# PCIE_dual_breakout_2L_v0_2.net
KiCad netlist of a schematic drawn in EAGLE
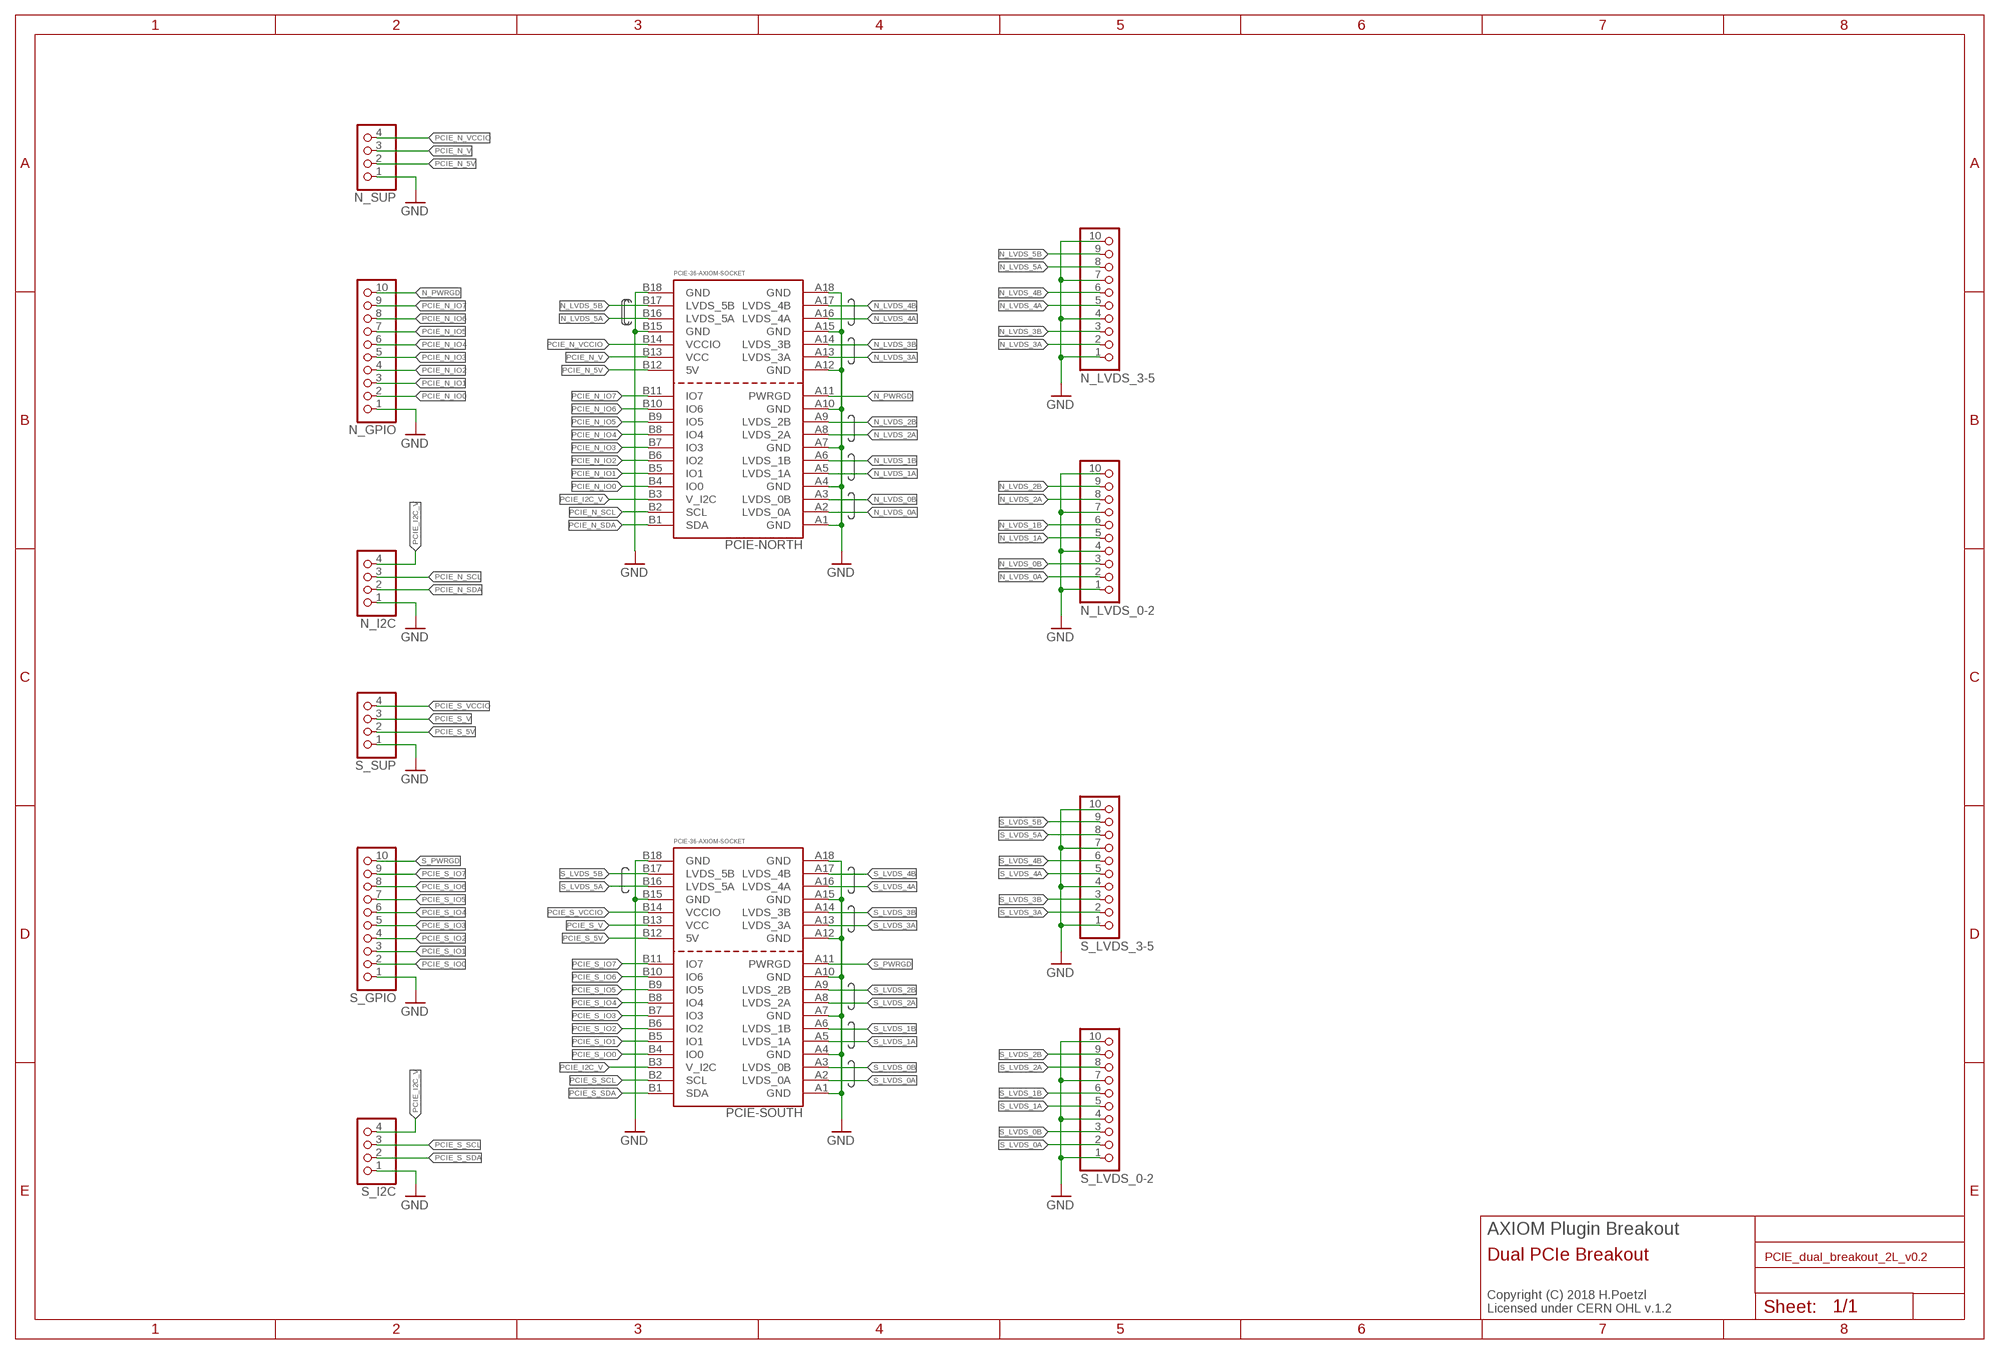
[diagram p0: schematic, sheet 1]

(export (version "E")
  (design (tool "Eeschema 10.0.6"))
  (components
    (comp (ref "N_GPIO")
      (value "PINHD-1X10_2.54-S")
      (footprint "eagle-import:1X10-S")
      (libsource (lib "eagle-import") (part "PINHD-1X10_2.54-S"))
    )
    (comp (ref "N_I2C")
      (value "PINHD-1X04_2.54-S")
      (footprint "eagle-import:1X04-S")
      (libsource (lib "eagle-import") (part "PINHD-1X04_2.54-S"))
    )
    (comp (ref "N_LVDS_0-2")
      (value "PINHD-1X10_2.54-S")
      (footprint "eagle-import:1X10-S")
      (libsource (lib "eagle-import") (part "PINHD-1X10_2.54-S"))
    )
    (comp (ref "N_LVDS_3-5")
      (value "PINHD-1X10_2.54-S")
      (footprint "eagle-import:1X10-S")
      (libsource (lib "eagle-import") (part "PINHD-1X10_2.54-S"))
    )
    (comp (ref "N_SUP")
      (value "PINHD-1X04_2.54-S")
      (footprint "eagle-import:1X04-S")
      (libsource (lib "eagle-import") (part "PINHD-1X04_2.54-S"))
    )
    (comp (ref "PCIE-NORTH")
      (value "PCIE-36-AXIOM-SOCKET")
      (footprint "eagle-import:PCIE-36")
      (libsource (lib "eagle-import") (part "PCIE-36-AXIOM-SOCKET"))
    )
    (comp (ref "PCIE-SOUTH")
      (value "PCIE-36-AXIOM-SOCKET")
      (footprint "eagle-import:PCIE-36")
      (libsource (lib "eagle-import") (part "PCIE-36-AXIOM-SOCKET"))
    )
    (comp (ref "S_GPIO")
      (value "PINHD-1X10_2.54-S")
      (footprint "eagle-import:1X10-S")
      (libsource (lib "eagle-import") (part "PINHD-1X10_2.54-S"))
    )
    (comp (ref "S_I2C")
      (value "PINHD-1X04_2.54-S")
      (footprint "eagle-import:1X04-S")
      (libsource (lib "eagle-import") (part "PINHD-1X04_2.54-S"))
    )
    (comp (ref "S_LVDS_0-2")
      (value "PINHD-1X10_2.54-S")
      (footprint "eagle-import:1X10-S")
      (libsource (lib "eagle-import") (part "PINHD-1X10_2.54-S"))
    )
    (comp (ref "S_LVDS_3-5")
      (value "PINHD-1X10_2.54-S")
      (footprint "eagle-import:1X10-S")
      (libsource (lib "eagle-import") (part "PINHD-1X10_2.54-S"))
    )
    (comp (ref "S_SUP")
      (value "PINHD-1X04_2.54-S")
      (footprint "eagle-import:1X04-S")
      (libsource (lib "eagle-import") (part "PINHD-1X04_2.54-S"))
    )
  )
  (nets
    (net (code "1") (name "GND") (class "Default")
      (node (ref "N_GPIO") (pin "1") (pinfunction "1_1") (pintype "passive"))
      (node (ref "N_I2C") (pin "1") (pinfunction "1_1") (pintype "passive"))
      (node (ref "N_LVDS_0-2") (pin "1") (pinfunction "1_1") (pintype "passive"))
      (node (ref "N_LVDS_0-2") (pin "10") (pinfunction "10_10") (pintype "passive"))
      (node (ref "N_LVDS_0-2") (pin "4") (pinfunction "4_4") (pintype "passive"))
      (node (ref "N_LVDS_0-2") (pin "7") (pinfunction "7_7") (pintype "passive"))
      (node (ref "N_LVDS_3-5") (pin "1") (pinfunction "1_1") (pintype "passive"))
      (node (ref "N_LVDS_3-5") (pin "10") (pinfunction "10_10") (pintype "passive"))
      (node (ref "N_LVDS_3-5") (pin "4") (pinfunction "4_4") (pintype "passive"))
      (node (ref "N_LVDS_3-5") (pin "7") (pinfunction "7_7") (pintype "passive"))
      (node (ref "N_SUP") (pin "1") (pinfunction "1_1") (pintype "passive"))
      (node (ref "PCIE-NORTH") (pin "A1") (pinfunction "GND_A1") (pintype "passive"))
      (node (ref "PCIE-NORTH") (pin "A10") (pinfunction "GND_A10") (pintype "passive"))
      (node (ref "PCIE-NORTH") (pin "A12") (pinfunction "GND_A12") (pintype "passive"))
      (node (ref "PCIE-NORTH") (pin "A15") (pinfunction "GND_A15") (pintype "passive"))
      (node (ref "PCIE-NORTH") (pin "A18") (pinfunction "GND_A18") (pintype "passive"))
      (node (ref "PCIE-NORTH") (pin "A4") (pinfunction "GND_A4") (pintype "passive"))
      (node (ref "PCIE-NORTH") (pin "A7") (pinfunction "GND_A7") (pintype "passive"))
      (node (ref "PCIE-NORTH") (pin "B15") (pinfunction "GND_B15") (pintype "passive"))
      (node (ref "PCIE-NORTH") (pin "B18") (pinfunction "GND_B18") (pintype "passive"))
      (node (ref "PCIE-SOUTH") (pin "A1") (pinfunction "GND_A1") (pintype "passive"))
      (node (ref "PCIE-SOUTH") (pin "A10") (pinfunction "GND_A10") (pintype "passive"))
      (node (ref "PCIE-SOUTH") (pin "A12") (pinfunction "GND_A12") (pintype "passive"))
      (node (ref "PCIE-SOUTH") (pin "A15") (pinfunction "GND_A15") (pintype "passive"))
      (node (ref "PCIE-SOUTH") (pin "A18") (pinfunction "GND_A18") (pintype "passive"))
      (node (ref "PCIE-SOUTH") (pin "A4") (pinfunction "GND_A4") (pintype "passive"))
      (node (ref "PCIE-SOUTH") (pin "A7") (pinfunction "GND_A7") (pintype "passive"))
      (node (ref "PCIE-SOUTH") (pin "B15") (pinfunction "GND_B15") (pintype "passive"))
      (node (ref "PCIE-SOUTH") (pin "B18") (pinfunction "GND_B18") (pintype "passive"))
      (node (ref "S_GPIO") (pin "1") (pinfunction "1_1") (pintype "passive"))
      (node (ref "S_I2C") (pin "1") (pinfunction "1_1") (pintype "passive"))
      (node (ref "S_LVDS_0-2") (pin "1") (pinfunction "1_1") (pintype "passive"))
      (node (ref "S_LVDS_0-2") (pin "10") (pinfunction "10_10") (pintype "passive"))
      (node (ref "S_LVDS_0-2") (pin "4") (pinfunction "4_4") (pintype "passive"))
      (node (ref "S_LVDS_0-2") (pin "7") (pinfunction "7_7") (pintype "passive"))
      (node (ref "S_LVDS_3-5") (pin "1") (pinfunction "1_1") (pintype "passive"))
      (node (ref "S_LVDS_3-5") (pin "10") (pinfunction "10_10") (pintype "passive"))
      (node (ref "S_LVDS_3-5") (pin "4") (pinfunction "4_4") (pintype "passive"))
      (node (ref "S_LVDS_3-5") (pin "7") (pinfunction "7_7") (pintype "passive"))
      (node (ref "S_SUP") (pin "1") (pinfunction "1_1") (pintype "passive"))
    )
    (net (code "2") (name "N_LVDS_0A") (class "Default")
      (node (ref "N_LVDS_0-2") (pin "2") (pinfunction "2_2") (pintype "passive"))
      (node (ref "PCIE-NORTH") (pin "A2") (pinfunction "LVDS_0A_A2") (pintype "passive"))
    )
    (net (code "3") (name "N_LVDS_0B") (class "Default")
      (node (ref "N_LVDS_0-2") (pin "3") (pinfunction "3_3") (pintype "passive"))
      (node (ref "PCIE-NORTH") (pin "A3") (pinfunction "LVDS_0B_A3") (pintype "passive"))
    )
    (net (code "4") (name "N_LVDS_1A") (class "Default")
      (node (ref "N_LVDS_0-2") (pin "5") (pinfunction "5_5") (pintype "passive"))
      (node (ref "PCIE-NORTH") (pin "A5") (pinfunction "LVDS_1A_A5") (pintype "passive"))
    )
    (net (code "5") (name "N_LVDS_1B") (class "Default")
      (node (ref "N_LVDS_0-2") (pin "6") (pinfunction "6_6") (pintype "passive"))
      (node (ref "PCIE-NORTH") (pin "A6") (pinfunction "LVDS_1B_A6") (pintype "passive"))
    )
    (net (code "6") (name "N_LVDS_2A") (class "Default")
      (node (ref "N_LVDS_0-2") (pin "8") (pinfunction "8_8") (pintype "passive"))
      (node (ref "PCIE-NORTH") (pin "A8") (pinfunction "LVDS_2A_A8") (pintype "passive"))
    )
    (net (code "7") (name "N_LVDS_2B") (class "Default")
      (node (ref "N_LVDS_0-2") (pin "9") (pinfunction "9_9") (pintype "passive"))
      (node (ref "PCIE-NORTH") (pin "A9") (pinfunction "LVDS_2B_A9") (pintype "passive"))
    )
    (net (code "8") (name "N_LVDS_3A") (class "Default")
      (node (ref "N_LVDS_3-5") (pin "2") (pinfunction "2_2") (pintype "passive"))
      (node (ref "PCIE-NORTH") (pin "A13") (pinfunction "LVDS_3A_A13") (pintype "passive"))
    )
    (net (code "9") (name "N_LVDS_3B") (class "Default")
      (node (ref "N_LVDS_3-5") (pin "3") (pinfunction "3_3") (pintype "passive"))
      (node (ref "PCIE-NORTH") (pin "A14") (pinfunction "LVDS_3B_A14") (pintype "passive"))
    )
    (net (code "10") (name "N_LVDS_4A") (class "Default")
      (node (ref "N_LVDS_3-5") (pin "5") (pinfunction "5_5") (pintype "passive"))
      (node (ref "PCIE-NORTH") (pin "A16") (pinfunction "LVDS_4A_A16") (pintype "passive"))
    )
    (net (code "11") (name "N_LVDS_4B") (class "Default")
      (node (ref "N_LVDS_3-5") (pin "6") (pinfunction "6_6") (pintype "passive"))
      (node (ref "PCIE-NORTH") (pin "A17") (pinfunction "LVDS_4B_A17") (pintype "passive"))
    )
    (net (code "12") (name "N_LVDS_5A") (class "Default")
      (node (ref "N_LVDS_3-5") (pin "8") (pinfunction "8_8") (pintype "passive"))
      (node (ref "PCIE-NORTH") (pin "B16") (pinfunction "LVDS_5A_B16") (pintype "passive"))
    )
    (net (code "13") (name "N_LVDS_5B") (class "Default")
      (node (ref "N_LVDS_3-5") (pin "9") (pinfunction "9_9") (pintype "passive"))
      (node (ref "PCIE-NORTH") (pin "B17") (pinfunction "LVDS_5B_B17") (pintype "passive"))
    )
    (net (code "14") (name "N_PWRGD") (class "Default")
      (node (ref "N_GPIO") (pin "10") (pinfunction "10_10") (pintype "passive"))
      (node (ref "PCIE-NORTH") (pin "A11") (pinfunction "PWRGD_A11") (pintype "passive"))
    )
    (net (code "15") (name "PCIE_I2C_V") (class "Default")
      (node (ref "N_I2C") (pin "4") (pinfunction "4_4") (pintype "passive"))
      (node (ref "PCIE-NORTH") (pin "B3") (pinfunction "V_I2C_B3") (pintype "passive"))
      (node (ref "PCIE-SOUTH") (pin "B3") (pinfunction "V_I2C_B3") (pintype "passive"))
      (node (ref "S_I2C") (pin "4") (pinfunction "4_4") (pintype "passive"))
    )
    (net (code "16") (name "PCIE_N_5V") (class "Default")
      (node (ref "N_SUP") (pin "2") (pinfunction "2_2") (pintype "passive"))
      (node (ref "PCIE-NORTH") (pin "B12") (pinfunction "5V_B12") (pintype "passive"))
    )
    (net (code "17") (name "PCIE_N_IO0") (class "Default")
      (node (ref "N_GPIO") (pin "2") (pinfunction "2_2") (pintype "passive"))
      (node (ref "PCIE-NORTH") (pin "B4") (pinfunction "IO0_B4") (pintype "passive"))
    )
    (net (code "18") (name "PCIE_N_IO1") (class "Default")
      (node (ref "N_GPIO") (pin "3") (pinfunction "3_3") (pintype "passive"))
      (node (ref "PCIE-NORTH") (pin "B5") (pinfunction "IO1_B5") (pintype "passive"))
    )
    (net (code "19") (name "PCIE_N_IO2") (class "Default")
      (node (ref "N_GPIO") (pin "4") (pinfunction "4_4") (pintype "passive"))
      (node (ref "PCIE-NORTH") (pin "B6") (pinfunction "IO2_B6") (pintype "passive"))
    )
    (net (code "20") (name "PCIE_N_IO3") (class "Default")
      (node (ref "N_GPIO") (pin "5") (pinfunction "5_5") (pintype "passive"))
      (node (ref "PCIE-NORTH") (pin "B7") (pinfunction "IO3_B7") (pintype "passive"))
    )
    (net (code "21") (name "PCIE_N_IO4") (class "Default")
      (node (ref "N_GPIO") (pin "6") (pinfunction "6_6") (pintype "passive"))
      (node (ref "PCIE-NORTH") (pin "B8") (pinfunction "IO4_B8") (pintype "passive"))
    )
    (net (code "22") (name "PCIE_N_IO5") (class "Default")
      (node (ref "N_GPIO") (pin "7") (pinfunction "7_7") (pintype "passive"))
      (node (ref "PCIE-NORTH") (pin "B9") (pinfunction "IO5_B9") (pintype "passive"))
    )
    (net (code "23") (name "PCIE_N_IO6") (class "Default")
      (node (ref "N_GPIO") (pin "8") (pinfunction "8_8") (pintype "passive"))
      (node (ref "PCIE-NORTH") (pin "B10") (pinfunction "IO6_B10") (pintype "passive"))
    )
    (net (code "24") (name "PCIE_N_IO7") (class "Default")
      (node (ref "N_GPIO") (pin "9") (pinfunction "9_9") (pintype "passive"))
      (node (ref "PCIE-NORTH") (pin "B11") (pinfunction "IO7_B11") (pintype "passive"))
    )
    (net (code "25") (name "PCIE_N_SCL") (class "Default")
      (node (ref "N_I2C") (pin "3") (pinfunction "3_3") (pintype "passive"))
      (node (ref "PCIE-NORTH") (pin "B2") (pinfunction "SCL_B2") (pintype "passive"))
    )
    (net (code "26") (name "PCIE_N_SDA") (class "Default")
      (node (ref "N_I2C") (pin "2") (pinfunction "2_2") (pintype "passive"))
      (node (ref "PCIE-NORTH") (pin "B1") (pinfunction "SDA_B1") (pintype "passive"))
    )
    (net (code "27") (name "PCIE_N_V") (class "Default")
      (node (ref "N_SUP") (pin "3") (pinfunction "3_3") (pintype "passive"))
      (node (ref "PCIE-NORTH") (pin "B13") (pinfunction "VCC_B13") (pintype "passive"))
    )
    (net (code "28") (name "PCIE_N_VCCIO") (class "Default")
      (node (ref "N_SUP") (pin "4") (pinfunction "4_4") (pintype "passive"))
      (node (ref "PCIE-NORTH") (pin "B14") (pinfunction "VCCIO_B14") (pintype "passive"))
    )
    (net (code "29") (name "PCIE_S_5V") (class "Default")
      (node (ref "PCIE-SOUTH") (pin "B12") (pinfunction "5V_B12") (pintype "passive"))
      (node (ref "S_SUP") (pin "2") (pinfunction "2_2") (pintype "passive"))
    )
    (net (code "30") (name "PCIE_S_IO0") (class "Default")
      (node (ref "PCIE-SOUTH") (pin "B4") (pinfunction "IO0_B4") (pintype "passive"))
      (node (ref "S_GPIO") (pin "2") (pinfunction "2_2") (pintype "passive"))
    )
    (net (code "31") (name "PCIE_S_IO1") (class "Default")
      (node (ref "PCIE-SOUTH") (pin "B5") (pinfunction "IO1_B5") (pintype "passive"))
      (node (ref "S_GPIO") (pin "3") (pinfunction "3_3") (pintype "passive"))
    )
    (net (code "32") (name "PCIE_S_IO2") (class "Default")
      (node (ref "PCIE-SOUTH") (pin "B6") (pinfunction "IO2_B6") (pintype "passive"))
      (node (ref "S_GPIO") (pin "4") (pinfunction "4_4") (pintype "passive"))
    )
    (net (code "33") (name "PCIE_S_IO3") (class "Default")
      (node (ref "PCIE-SOUTH") (pin "B7") (pinfunction "IO3_B7") (pintype "passive"))
      (node (ref "S_GPIO") (pin "5") (pinfunction "5_5") (pintype "passive"))
    )
    (net (code "34") (name "PCIE_S_IO4") (class "Default")
      (node (ref "PCIE-SOUTH") (pin "B8") (pinfunction "IO4_B8") (pintype "passive"))
      (node (ref "S_GPIO") (pin "6") (pinfunction "6_6") (pintype "passive"))
    )
    (net (code "35") (name "PCIE_S_IO5") (class "Default")
      (node (ref "PCIE-SOUTH") (pin "B9") (pinfunction "IO5_B9") (pintype "passive"))
      (node (ref "S_GPIO") (pin "7") (pinfunction "7_7") (pintype "passive"))
    )
    (net (code "36") (name "PCIE_S_IO6") (class "Default")
      (node (ref "PCIE-SOUTH") (pin "B10") (pinfunction "IO6_B10") (pintype "passive"))
      (node (ref "S_GPIO") (pin "8") (pinfunction "8_8") (pintype "passive"))
    )
    (net (code "37") (name "PCIE_S_IO7") (class "Default")
      (node (ref "PCIE-SOUTH") (pin "B11") (pinfunction "IO7_B11") (pintype "passive"))
      (node (ref "S_GPIO") (pin "9") (pinfunction "9_9") (pintype "passive"))
    )
    (net (code "38") (name "PCIE_S_SCL") (class "Default")
      (node (ref "PCIE-SOUTH") (pin "B2") (pinfunction "SCL_B2") (pintype "passive"))
      (node (ref "S_I2C") (pin "3") (pinfunction "3_3") (pintype "passive"))
    )
    (net (code "39") (name "PCIE_S_SDA") (class "Default")
      (node (ref "PCIE-SOUTH") (pin "B1") (pinfunction "SDA_B1") (pintype "passive"))
      (node (ref "S_I2C") (pin "2") (pinfunction "2_2") (pintype "passive"))
    )
    (net (code "40") (name "PCIE_S_V") (class "Default")
      (node (ref "PCIE-SOUTH") (pin "B13") (pinfunction "VCC_B13") (pintype "passive"))
      (node (ref "S_SUP") (pin "3") (pinfunction "3_3") (pintype "passive"))
    )
    (net (code "41") (name "PCIE_S_VCCIO") (class "Default")
      (node (ref "PCIE-SOUTH") (pin "B14") (pinfunction "VCCIO_B14") (pintype "passive"))
      (node (ref "S_SUP") (pin "4") (pinfunction "4_4") (pintype "passive"))
    )
    (net (code "42") (name "S_LVDS_0A") (class "Default")
      (node (ref "PCIE-SOUTH") (pin "A2") (pinfunction "LVDS_0A_A2") (pintype "passive"))
      (node (ref "S_LVDS_0-2") (pin "2") (pinfunction "2_2") (pintype "passive"))
    )
    (net (code "43") (name "S_LVDS_0B") (class "Default")
      (node (ref "PCIE-SOUTH") (pin "A3") (pinfunction "LVDS_0B_A3") (pintype "passive"))
      (node (ref "S_LVDS_0-2") (pin "3") (pinfunction "3_3") (pintype "passive"))
    )
    (net (code "44") (name "S_LVDS_1A") (class "Default")
      (node (ref "PCIE-SOUTH") (pin "A5") (pinfunction "LVDS_1A_A5") (pintype "passive"))
      (node (ref "S_LVDS_0-2") (pin "5") (pinfunction "5_5") (pintype "passive"))
    )
    (net (code "45") (name "S_LVDS_1B") (class "Default")
      (node (ref "PCIE-SOUTH") (pin "A6") (pinfunction "LVDS_1B_A6") (pintype "passive"))
      (node (ref "S_LVDS_0-2") (pin "6") (pinfunction "6_6") (pintype "passive"))
    )
    (net (code "46") (name "S_LVDS_2A") (class "Default")
      (node (ref "PCIE-SOUTH") (pin "A8") (pinfunction "LVDS_2A_A8") (pintype "passive"))
      (node (ref "S_LVDS_0-2") (pin "8") (pinfunction "8_8") (pintype "passive"))
    )
    (net (code "47") (name "S_LVDS_2B") (class "Default")
      (node (ref "PCIE-SOUTH") (pin "A9") (pinfunction "LVDS_2B_A9") (pintype "passive"))
      (node (ref "S_LVDS_0-2") (pin "9") (pinfunction "9_9") (pintype "passive"))
    )
    (net (code "48") (name "S_LVDS_3A") (class "Default")
      (node (ref "PCIE-SOUTH") (pin "A13") (pinfunction "LVDS_3A_A13") (pintype "passive"))
      (node (ref "S_LVDS_3-5") (pin "2") (pinfunction "2_2") (pintype "passive"))
    )
    (net (code "49") (name "S_LVDS_3B") (class "Default")
      (node (ref "PCIE-SOUTH") (pin "A14") (pinfunction "LVDS_3B_A14") (pintype "passive"))
      (node (ref "S_LVDS_3-5") (pin "3") (pinfunction "3_3") (pintype "passive"))
    )
    (net (code "50") (name "S_LVDS_4A") (class "Default")
      (node (ref "PCIE-SOUTH") (pin "A16") (pinfunction "LVDS_4A_A16") (pintype "passive"))
      (node (ref "S_LVDS_3-5") (pin "5") (pinfunction "5_5") (pintype "passive"))
    )
    (net (code "51") (name "S_LVDS_4B") (class "Default")
      (node (ref "PCIE-SOUTH") (pin "A17") (pinfunction "LVDS_4B_A17") (pintype "passive"))
      (node (ref "S_LVDS_3-5") (pin "6") (pinfunction "6_6") (pintype "passive"))
    )
    (net (code "52") (name "S_LVDS_5A") (class "Default")
      (node (ref "PCIE-SOUTH") (pin "B16") (pinfunction "LVDS_5A_B16") (pintype "passive"))
      (node (ref "S_LVDS_3-5") (pin "8") (pinfunction "8_8") (pintype "passive"))
    )
    (net (code "53") (name "S_LVDS_5B") (class "Default")
      (node (ref "PCIE-SOUTH") (pin "B17") (pinfunction "LVDS_5B_B17") (pintype "passive"))
      (node (ref "S_LVDS_3-5") (pin "9") (pinfunction "9_9") (pintype "passive"))
    )
    (net (code "54") (name "S_PWRGD") (class "Default")
      (node (ref "PCIE-SOUTH") (pin "A11") (pinfunction "PWRGD_A11") (pintype "passive"))
      (node (ref "S_GPIO") (pin "10") (pinfunction "10_10") (pintype "passive"))
    )
  )
)
